# DM1097_Connector_B.net
KiCad netlist of a schematic drawn in Altium Designer
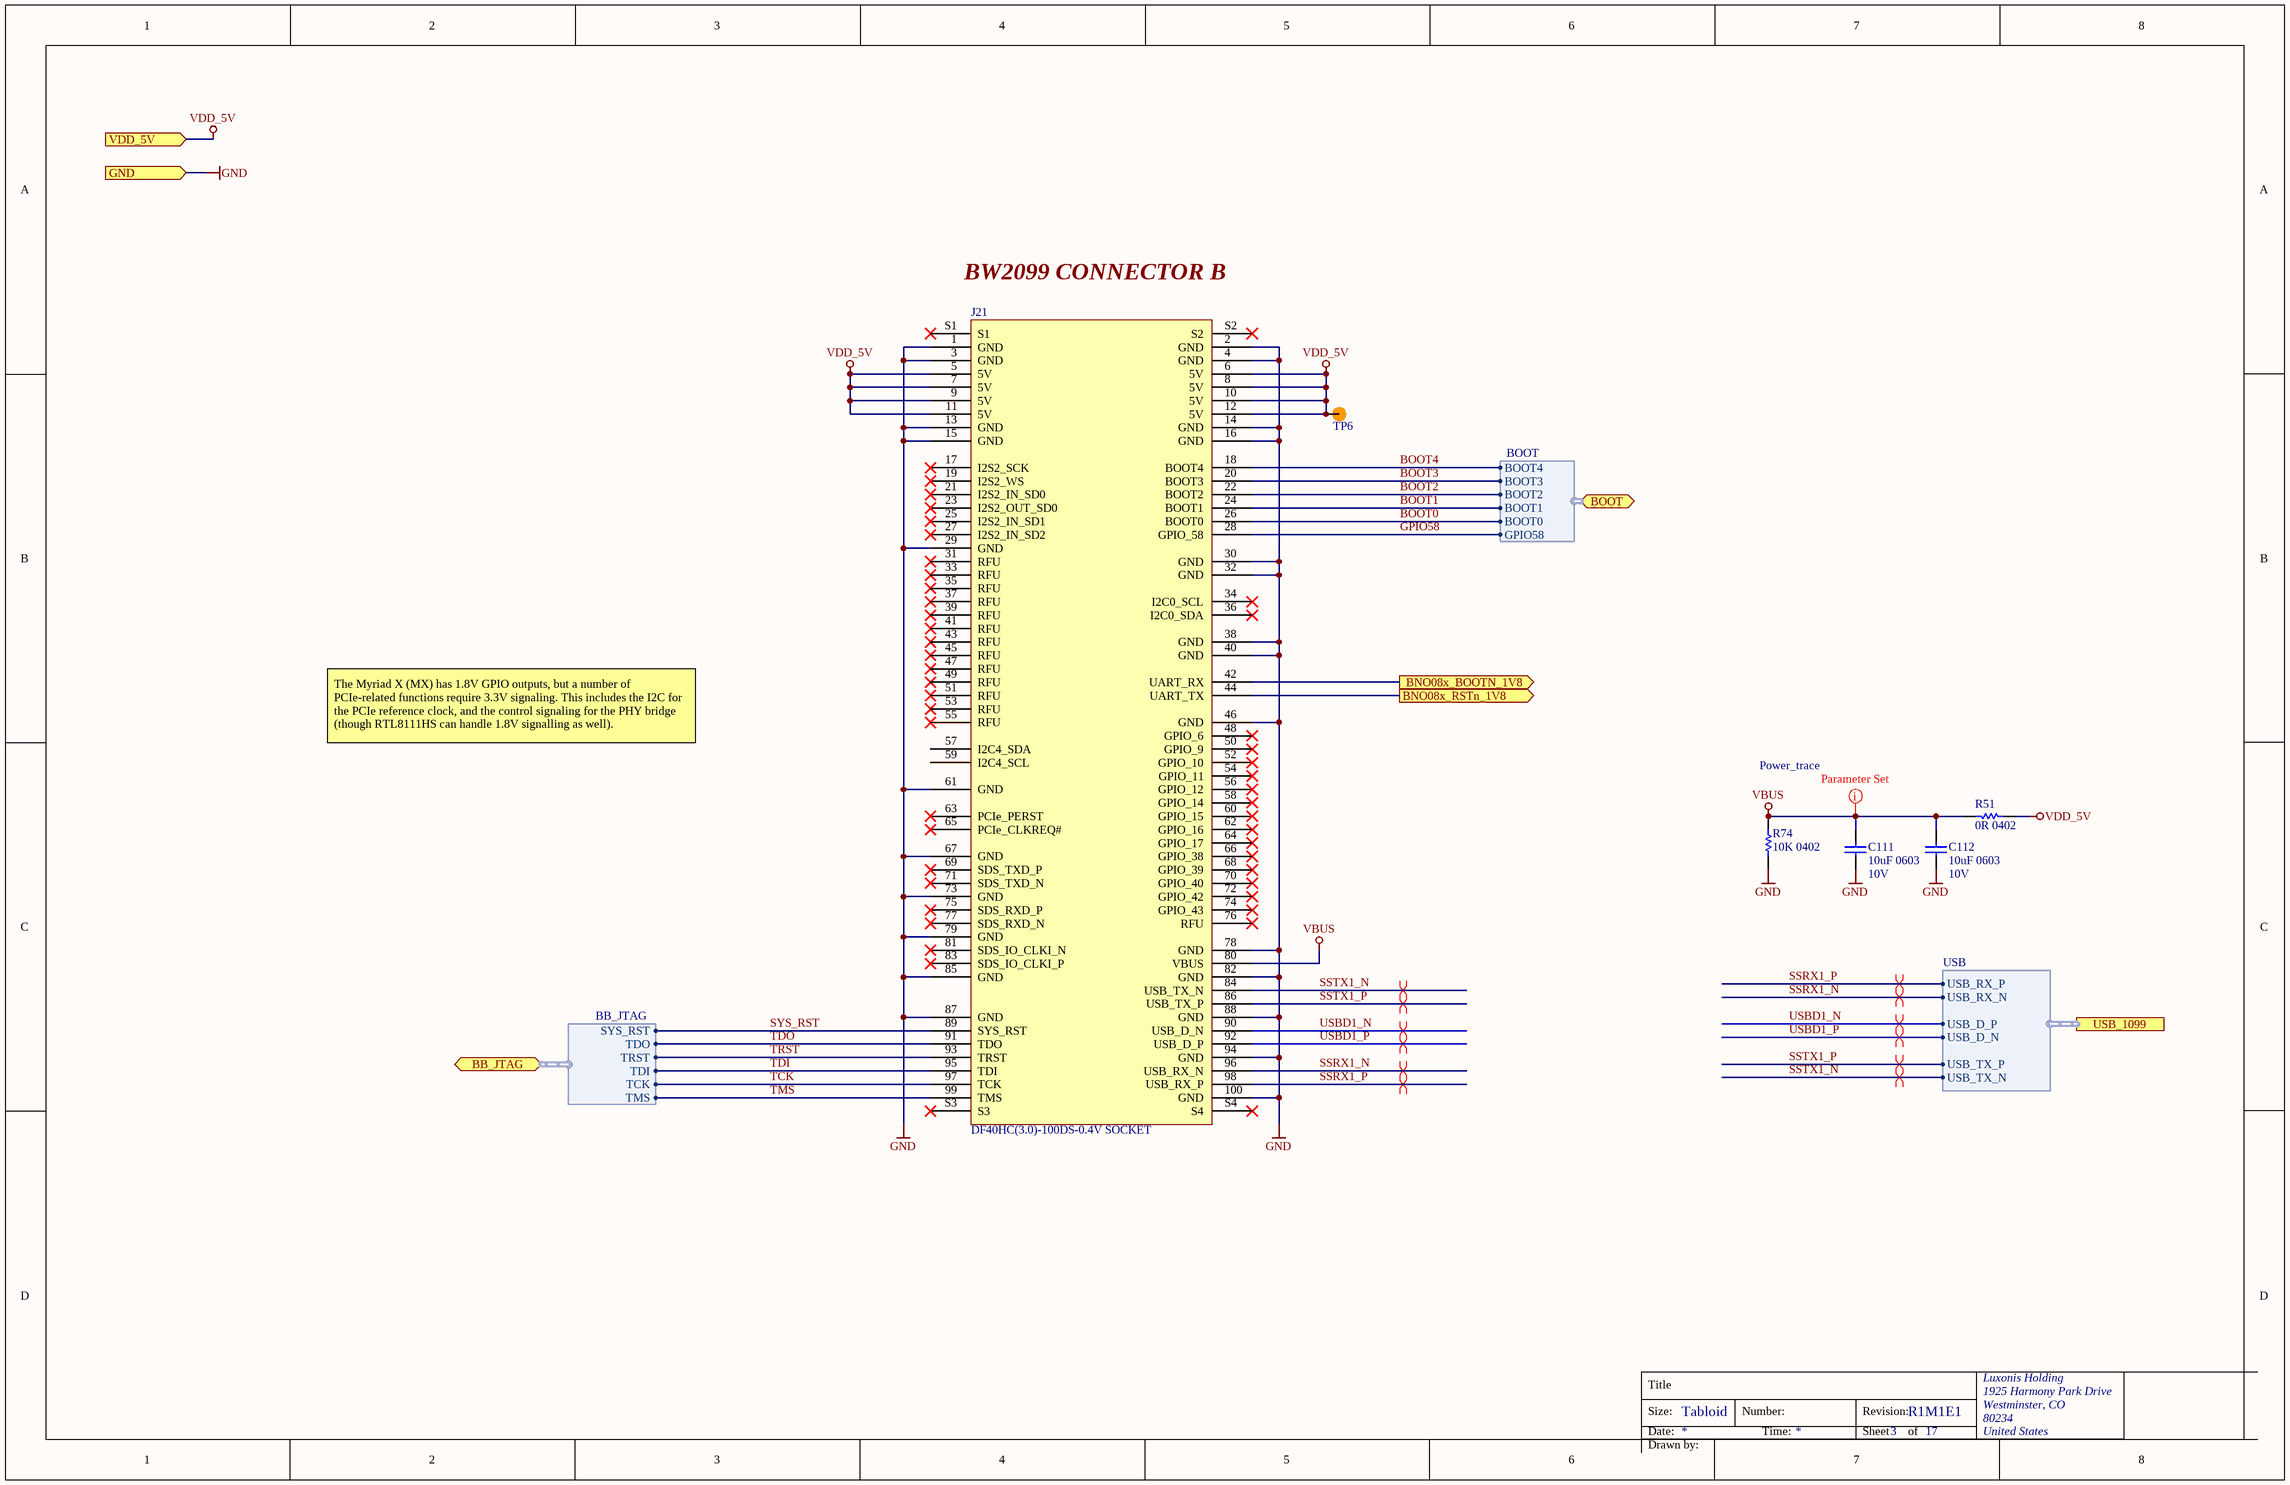
[diagram p0: DM1097_Connector_B.SchDoc]

(export (version "E")
  (design (tool "Eeschema 10.0.6"))
  (components
    (comp (ref "C111")
      (value "10uF 0603")
      (footprint "CAP_Altium_Vault_Generic:CAPC0603(1608)100_N")
      (description "CAP CER 10UF 10V X5R 0603 20%")
      (fields (field (name "TOLERANCE") "20%") (field (name "VOLTAGE RATING") "10V"))
      (libsource (lib "LuxonisMaster") (part "GRM188R61A106ME69D"))
    )
    (comp (ref "C112")
      (value "10uF 0603")
      (footprint "CAP_Altium_Vault_Generic:CAPC0603(1608)100_N")
      (description "CAP CER 10UF 10V X5R 0603 20%")
      (fields (field (name "TOLERANCE") "20%") (field (name "VOLTAGE RATING") "10V"))
      (libsource (lib "LuxonisMaster") (part "GRM188R61A106ME69D"))
    )
    (comp (ref "J21")
      (value "DF40HC(3.0)-100DS-0.4V SOCKET")
      (footprint "DF40HC-3.0-100DS-0.4V_minpad")
      (description "Conn Board to Board RCP 100 POS 0.4mm Solder ST SMD T/R")
      (libsource (lib "LuxonisMaster_OPAL") (part "BW2099_SCKT_Conn_B"))
    )
    (comp (ref "R51")
      (value "0R 0402")
      (footprint "RES_Altium_Vault_Generic:RESC0402(1005)_N")
      (description "RES SMD 0 OHM JUMPER 1/16W 0402")
      (fields (field (name "TOLERANCE") "5%"))
      (libsource (lib "LuxonisMaster") (part "CRCW04020000Z0ED"))
    )
    (comp (ref "R74")
      (value "10K 0402")
      (footprint "RES_Altium_Vault_Generic:RESC0402(1005)_N")
      (fields (field (name "TOLERANCE") "1%"))
      (libsource (lib "LuxonisMaster") (part "RC0402FR-1310KL"))
    )
    (comp (ref "TP6")
      (value "TP100_200_NS")
      (footprint "LuxonisMaster:TP100_200_NS")
      (libsource (lib "LuxonisMaster") (part "TEST_POINT"))
    )
  )
  (nets
    (net (code "4") (name "/BNO08x_BOOTN_1V8") (class "Default")
      (node (ref "J21") (pin "42") (pinfunction "UART_RX_42") (pintype "passive"))
    )
    (net (code "5") (name "/BNO08x_RSTn_1V8") (class "Default")
      (node (ref "J21") (pin "44") (pinfunction "UART_TX_44") (pintype "passive"))
    )
    (net (code "6") (name "/BOOT0") (class "Default")
      (node (ref "J21") (pin "26") (pinfunction "BOOT0_26") (pintype "passive"))
    )
    (net (code "7") (name "/BOOT1") (class "Default")
      (node (ref "J21") (pin "24") (pinfunction "BOOT1_24") (pintype "passive"))
    )
    (net (code "8") (name "/BOOT2") (class "Default")
      (node (ref "J21") (pin "22") (pinfunction "BOOT2_22") (pintype "passive"))
    )
    (net (code "9") (name "/BOOT3") (class "Default")
      (node (ref "J21") (pin "20") (pinfunction "BOOT3_20") (pintype "passive"))
    )
    (net (code "10") (name "/BOOT4") (class "Default")
      (node (ref "J21") (pin "18") (pinfunction "BOOT4_18") (pintype "passive"))
    )
    (net (code "11") (name "/GPIO58") (class "Default")
      (node (ref "J21") (pin "28") (pinfunction "GPIO_58_28") (pintype "passive"))
    )
    (net (code "12") (name "/SSRX1_N") (class "Default")
      (node (ref "J21") (pin "96") (pinfunction "USB_RX_N_96") (pintype "passive"))
    )
    (net (code "13") (name "/SSRX1_P") (class "Default")
      (node (ref "J21") (pin "98") (pinfunction "USB_RX_P_98") (pintype "passive"))
    )
    (net (code "14") (name "/SSTX1_N") (class "Default")
      (node (ref "J21") (pin "84") (pinfunction "USB_TX_N_84") (pintype "passive"))
    )
    (net (code "15") (name "/SSTX1_P") (class "Default")
      (node (ref "J21") (pin "86") (pinfunction "USB_TX_P_86") (pintype "passive"))
    )
    (net (code "16") (name "/SYS_RST") (class "Default")
      (node (ref "J21") (pin "89") (pinfunction "SYS_RST_89") (pintype "passive"))
    )
    (net (code "17") (name "/TCK") (class "Default")
      (node (ref "J21") (pin "97") (pinfunction "TCK_97") (pintype "passive"))
    )
    (net (code "18") (name "/TDI") (class "Default")
      (node (ref "J21") (pin "95") (pinfunction "TDI_95") (pintype "passive"))
    )
    (net (code "19") (name "/TDO") (class "Default")
      (node (ref "J21") (pin "91") (pinfunction "TDO_91") (pintype "passive"))
    )
    (net (code "20") (name "/TMS") (class "Default")
      (node (ref "J21") (pin "99") (pinfunction "TMS_99") (pintype "passive"))
    )
    (net (code "21") (name "/TRST") (class "Default")
      (node (ref "J21") (pin "93") (pinfunction "TRST_93") (pintype "passive"))
    )
    (net (code "22") (name "/USBD1_N") (class "Default")
      (node (ref "J21") (pin "90") (pinfunction "USB_D_N_90") (pintype "passive"))
    )
    (net (code "23") (name "/USBD1_P") (class "Default")
      (node (ref "J21") (pin "92") (pinfunction "USB_D_P_92") (pintype "passive"))
    )
    (net (code "27") (name "GND") (class "Default")
      (node (ref "C111") (pin "1") (pinfunction "1_1") (pintype "passive"))
      (node (ref "C112") (pin "1") (pinfunction "1_1") (pintype "passive"))
      (node (ref "J21") (pin "1") (pinfunction "GND_1") (pintype "passive"))
      (node (ref "J21") (pin "100") (pinfunction "GND_100") (pintype "passive"))
      (node (ref "J21") (pin "13") (pinfunction "GND_13") (pintype "passive"))
      (node (ref "J21") (pin "14") (pinfunction "GND_14") (pintype "passive"))
      (node (ref "J21") (pin "15") (pinfunction "GND_15") (pintype "passive"))
      (node (ref "J21") (pin "16") (pinfunction "GND_16") (pintype "passive"))
      (node (ref "J21") (pin "2") (pinfunction "GND_2") (pintype "passive"))
      (node (ref "J21") (pin "29") (pinfunction "GND_29") (pintype "passive"))
      (node (ref "J21") (pin "3") (pinfunction "GND_3") (pintype "passive"))
      (node (ref "J21") (pin "30") (pinfunction "GND_30") (pintype "passive"))
      (node (ref "J21") (pin "32") (pinfunction "GND_32") (pintype "passive"))
      (node (ref "J21") (pin "38") (pinfunction "GND_38") (pintype "passive"))
      (node (ref "J21") (pin "4") (pinfunction "GND_4") (pintype "passive"))
      (node (ref "J21") (pin "40") (pinfunction "GND_40") (pintype "passive"))
      (node (ref "J21") (pin "46") (pinfunction "GND_46") (pintype "passive"))
      (node (ref "J21") (pin "61") (pinfunction "GND_61") (pintype "passive"))
      (node (ref "J21") (pin "67") (pinfunction "GND_67") (pintype "passive"))
      (node (ref "J21") (pin "73") (pinfunction "GND_73") (pintype "passive"))
      (node (ref "J21") (pin "78") (pinfunction "GND_78") (pintype "passive"))
      (node (ref "J21") (pin "79") (pinfunction "GND_79") (pintype "passive"))
      (node (ref "J21") (pin "82") (pinfunction "GND_82") (pintype "passive"))
      (node (ref "J21") (pin "85") (pinfunction "GND_85") (pintype "passive"))
      (node (ref "J21") (pin "87") (pinfunction "GND_87") (pintype "passive"))
      (node (ref "J21") (pin "88") (pinfunction "GND_88") (pintype "passive"))
      (node (ref "J21") (pin "94") (pinfunction "GND_94") (pintype "passive"))
      (node (ref "R74") (pin "1") (pinfunction "1_1") (pintype "passive"))
    )
    (net (code "28") (name "VBUS") (class "Default")
      (node (ref "C111") (pin "2") (pinfunction "2_2") (pintype "passive"))
      (node (ref "C112") (pin "2") (pinfunction "2_2") (pintype "passive"))
      (node (ref "J21") (pin "80") (pinfunction "VBUS_80") (pintype "passive"))
      (node (ref "R51") (pin "1") (pinfunction "1_1") (pintype "passive"))
      (node (ref "R74") (pin "2") (pinfunction "2_2") (pintype "passive"))
    )
    (net (code "29") (name "VDD_5V") (class "Default")
      (node (ref "J21") (pin "10") (pinfunction "5V_10") (pintype "passive"))
      (node (ref "J21") (pin "11") (pinfunction "5V_11") (pintype "passive"))
      (node (ref "J21") (pin "12") (pinfunction "5V_12") (pintype "passive"))
      (node (ref "J21") (pin "5") (pinfunction "5V_5") (pintype "passive"))
      (node (ref "J21") (pin "6") (pinfunction "5V_6") (pintype "passive"))
      (node (ref "J21") (pin "7") (pinfunction "5V_7") (pintype "passive"))
      (node (ref "J21") (pin "8") (pinfunction "5V_8") (pintype "passive"))
      (node (ref "J21") (pin "9") (pinfunction "5V_9") (pintype "passive"))
      (node (ref "R51") (pin "2") (pinfunction "2_2") (pintype "passive"))
      (node (ref "TP6") (pin "1") (pintype "passive"))
    )
    (net (code "30") (name "unconnected-(J21-GPIO_6-Pad48)") (class "Default")
      (node (ref "J21") (pin "48") (pinfunction "GPIO_6_48") (pintype "passive+no_connect"))
    )
    (net (code "31") (name "unconnected-(J21-GPIO_9-Pad50)") (class "Default")
      (node (ref "J21") (pin "50") (pinfunction "GPIO_9_50") (pintype "passive+no_connect"))
    )
    (net (code "32") (name "unconnected-(J21-GPIO_10-Pad52)") (class "Default")
      (node (ref "J21") (pin "52") (pinfunction "GPIO_10_52") (pintype "passive+no_connect"))
    )
    (net (code "33") (name "unconnected-(J21-GPIO_11-Pad54)") (class "Default")
      (node (ref "J21") (pin "54") (pinfunction "GPIO_11_54") (pintype "passive+no_connect"))
    )
    (net (code "34") (name "unconnected-(J21-GPIO_12-Pad56)") (class "Default")
      (node (ref "J21") (pin "56") (pinfunction "GPIO_12_56") (pintype "passive+no_connect"))
    )
    (net (code "35") (name "unconnected-(J21-GPIO_14-Pad58)") (class "Default")
      (node (ref "J21") (pin "58") (pinfunction "GPIO_14_58") (pintype "passive+no_connect"))
    )
    (net (code "36") (name "unconnected-(J21-GPIO_15-Pad60)") (class "Default")
      (node (ref "J21") (pin "60") (pinfunction "GPIO_15_60") (pintype "passive+no_connect"))
    )
    (net (code "37") (name "unconnected-(J21-GPIO_16-Pad62)") (class "Default")
      (node (ref "J21") (pin "62") (pinfunction "GPIO_16_62") (pintype "passive+no_connect"))
    )
    (net (code "38") (name "unconnected-(J21-GPIO_17-Pad64)") (class "Default")
      (node (ref "J21") (pin "64") (pinfunction "GPIO_17_64") (pintype "passive+no_connect"))
    )
    (net (code "39") (name "unconnected-(J21-GPIO_38-Pad66)") (class "Default")
      (node (ref "J21") (pin "66") (pinfunction "GPIO_38_66") (pintype "passive+no_connect"))
    )
    (net (code "40") (name "unconnected-(J21-GPIO_39-Pad68)") (class "Default")
      (node (ref "J21") (pin "68") (pinfunction "GPIO_39_68") (pintype "passive+no_connect"))
    )
    (net (code "41") (name "unconnected-(J21-GPIO_40-Pad70)") (class "Default")
      (node (ref "J21") (pin "70") (pinfunction "GPIO_40_70") (pintype "passive+no_connect"))
    )
    (net (code "42") (name "unconnected-(J21-GPIO_42-Pad72)") (class "Default")
      (node (ref "J21") (pin "72") (pinfunction "GPIO_42_72") (pintype "passive+no_connect"))
    )
    (net (code "43") (name "unconnected-(J21-GPIO_43-Pad74)") (class "Default")
      (node (ref "J21") (pin "74") (pinfunction "GPIO_43_74") (pintype "passive+no_connect"))
    )
    (net (code "44") (name "unconnected-(J21-I2C0_SCL-Pad34)") (class "Default")
      (node (ref "J21") (pin "34") (pinfunction "I2C0_SCL_34") (pintype "passive+no_connect"))
    )
    (net (code "45") (name "unconnected-(J21-I2C0_SDA-Pad36)") (class "Default")
      (node (ref "J21") (pin "36") (pinfunction "I2C0_SDA_36") (pintype "passive+no_connect"))
    )
    (net (code "46") (name "unconnected-(J21-I2C4_SCL-Pad59)") (class "Default")
      (node (ref "J21") (pin "59") (pinfunction "I2C4_SCL_59") (pintype "passive"))
    )
    (net (code "47") (name "unconnected-(J21-I2C4_SDA-Pad57)") (class "Default")
      (node (ref "J21") (pin "57") (pinfunction "I2C4_SDA_57") (pintype "passive"))
    )
    (net (code "48") (name "unconnected-(J21-I2S2_IN_SD0-Pad21)") (class "Default")
      (node (ref "J21") (pin "21") (pinfunction "I2S2_IN_SD0_21") (pintype "passive+no_connect"))
    )
    (net (code "49") (name "unconnected-(J21-I2S2_IN_SD1-Pad25)") (class "Default")
      (node (ref "J21") (pin "25") (pinfunction "I2S2_IN_SD1_25") (pintype "passive+no_connect"))
    )
    (net (code "50") (name "unconnected-(J21-I2S2_IN_SD2-Pad27)") (class "Default")
      (node (ref "J21") (pin "27") (pinfunction "I2S2_IN_SD2_27") (pintype "passive+no_connect"))
    )
    (net (code "51") (name "unconnected-(J21-I2S2_OUT_SD0-Pad23)") (class "Default")
      (node (ref "J21") (pin "23") (pinfunction "I2S2_OUT_SD0_23") (pintype "passive+no_connect"))
    )
    (net (code "52") (name "unconnected-(J21-I2S2_SCK-Pad17)") (class "Default")
      (node (ref "J21") (pin "17") (pinfunction "I2S2_SCK_17") (pintype "passive+no_connect"))
    )
    (net (code "53") (name "unconnected-(J21-I2S2_WS-Pad19)") (class "Default")
      (node (ref "J21") (pin "19") (pinfunction "I2S2_WS_19") (pintype "passive+no_connect"))
    )
    (net (code "54") (name "unconnected-(J21-PCIe_CLKREQ#-Pad65)") (class "Default")
      (node (ref "J21") (pin "65") (pinfunction "PCIe_CLKREQ#_65") (pintype "passive+no_connect"))
    )
    (net (code "55") (name "unconnected-(J21-PCIe_PERST-Pad63)") (class "Default")
      (node (ref "J21") (pin "63") (pinfunction "PCIe_PERST_63") (pintype "passive+no_connect"))
    )
    (net (code "56") (name "unconnected-(J21-PadS1)") (class "Default")
      (node (ref "J21") (pin "S1") (pinfunction "S1_S1") (pintype "passive+no_connect"))
    )
    (net (code "57") (name "unconnected-(J21-PadS2)") (class "Default")
      (node (ref "J21") (pin "S2") (pinfunction "S2_S2") (pintype "passive+no_connect"))
    )
    (net (code "58") (name "unconnected-(J21-PadS3)") (class "Default")
      (node (ref "J21") (pin "S3") (pinfunction "S3_S3") (pintype "passive+no_connect"))
    )
    (net (code "59") (name "unconnected-(J21-PadS4)") (class "Default")
      (node (ref "J21") (pin "S4") (pinfunction "S4_S4") (pintype "passive+no_connect"))
    )
    (net (code "60") (name "unconnected-(J21-RFU-Pad31)") (class "Default")
      (node (ref "J21") (pin "31") (pinfunction "RFU_31") (pintype "passive+no_connect"))
    )
    (net (code "61") (name "unconnected-(J21-RFU-Pad33)") (class "Default")
      (node (ref "J21") (pin "33") (pinfunction "RFU_33") (pintype "passive+no_connect"))
    )
    (net (code "62") (name "unconnected-(J21-RFU-Pad35)") (class "Default")
      (node (ref "J21") (pin "35") (pinfunction "RFU_35") (pintype "passive+no_connect"))
    )
    (net (code "63") (name "unconnected-(J21-RFU-Pad37)") (class "Default")
      (node (ref "J21") (pin "37") (pinfunction "RFU_37") (pintype "passive+no_connect"))
    )
    (net (code "64") (name "unconnected-(J21-RFU-Pad39)") (class "Default")
      (node (ref "J21") (pin "39") (pinfunction "RFU_39") (pintype "passive+no_connect"))
    )
    (net (code "65") (name "unconnected-(J21-RFU-Pad41)") (class "Default")
      (node (ref "J21") (pin "41") (pinfunction "RFU_41") (pintype "passive+no_connect"))
    )
    (net (code "66") (name "unconnected-(J21-RFU-Pad43)") (class "Default")
      (node (ref "J21") (pin "43") (pinfunction "RFU_43") (pintype "passive+no_connect"))
    )
    (net (code "67") (name "unconnected-(J21-RFU-Pad45)") (class "Default")
      (node (ref "J21") (pin "45") (pinfunction "RFU_45") (pintype "passive+no_connect"))
    )
    (net (code "68") (name "unconnected-(J21-RFU-Pad47)") (class "Default")
      (node (ref "J21") (pin "47") (pinfunction "RFU_47") (pintype "passive+no_connect"))
    )
    (net (code "69") (name "unconnected-(J21-RFU-Pad49)") (class "Default")
      (node (ref "J21") (pin "49") (pinfunction "RFU_49") (pintype "passive+no_connect"))
    )
    (net (code "70") (name "unconnected-(J21-RFU-Pad51)") (class "Default")
      (node (ref "J21") (pin "51") (pinfunction "RFU_51") (pintype "passive+no_connect"))
    )
    (net (code "71") (name "unconnected-(J21-RFU-Pad53)") (class "Default")
      (node (ref "J21") (pin "53") (pinfunction "RFU_53") (pintype "passive+no_connect"))
    )
    (net (code "72") (name "unconnected-(J21-RFU-Pad55)") (class "Default")
      (node (ref "J21") (pin "55") (pinfunction "RFU_55") (pintype "passive+no_connect"))
    )
    (net (code "73") (name "unconnected-(J21-RFU-Pad76)") (class "Default")
      (node (ref "J21") (pin "76") (pinfunction "RFU_76") (pintype "passive+no_connect"))
    )
    (net (code "74") (name "unconnected-(J21-SDS_IO_CLKI_N-Pad81)") (class "Default")
      (node (ref "J21") (pin "81") (pinfunction "SDS_IO_CLKI_N_81") (pintype "passive+no_connect"))
    )
    (net (code "75") (name "unconnected-(J21-SDS_IO_CLKI_P-Pad83)") (class "Default")
      (node (ref "J21") (pin "83") (pinfunction "SDS_IO_CLKI_P_83") (pintype "passive+no_connect"))
    )
    (net (code "76") (name "unconnected-(J21-SDS_RXD_N-Pad77)") (class "Default")
      (node (ref "J21") (pin "77") (pinfunction "SDS_RXD_N_77") (pintype "passive+no_connect"))
    )
    (net (code "77") (name "unconnected-(J21-SDS_RXD_P-Pad75)") (class "Default")
      (node (ref "J21") (pin "75") (pinfunction "SDS_RXD_P_75") (pintype "passive+no_connect"))
    )
    (net (code "78") (name "unconnected-(J21-SDS_TXD_N-Pad71)") (class "Default")
      (node (ref "J21") (pin "71") (pinfunction "SDS_TXD_N_71") (pintype "passive+no_connect"))
    )
    (net (code "79") (name "unconnected-(J21-SDS_TXD_P-Pad69)") (class "Default")
      (node (ref "J21") (pin "69") (pinfunction "SDS_TXD_P_69") (pintype "passive+no_connect"))
    )
  )
)
